# Connections.net
KiCad netlist of a schematic drawn in Altium Designer
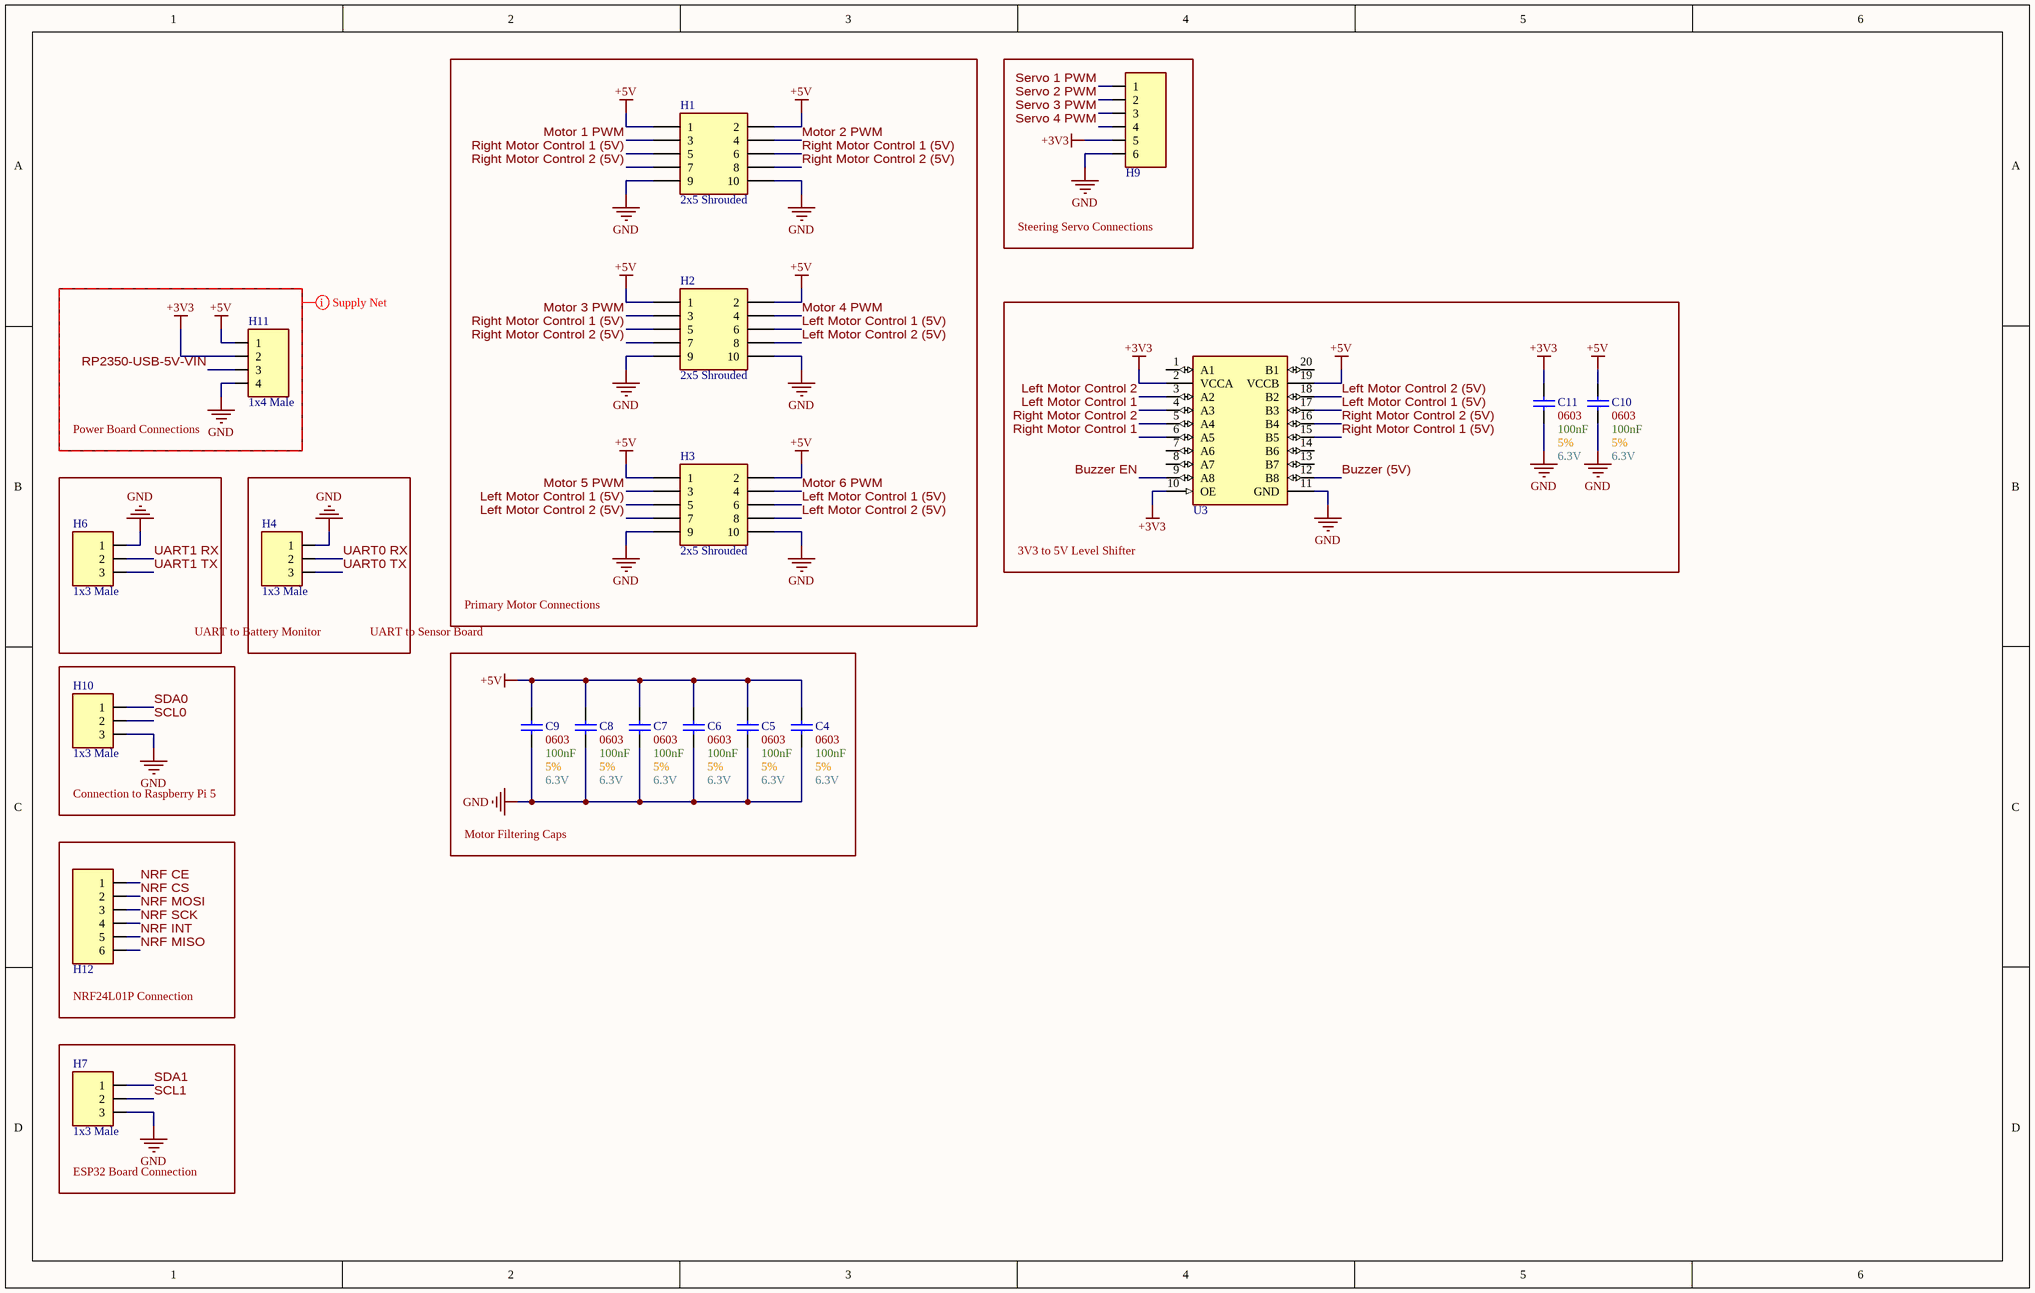
[diagram p0: Connections.SchDoc]

(export (version "E")
  (design (tool "Eeschema 10.0.6"))
  (components
    (comp (ref "C4")
      (value "[Cap] SMD Nonpolarized")
      (footprint "[Cap] SMD 0603")
      (fields
        (field (name "SIZE PACKAGE") "0603")
        (field (name "CAPACITANCE") "100nF")
        (field (name "VOLTAGE") "6.3V")
        (field (name "TOLERANCE") "5%")
      )
      (libsource (lib "RADM Components") (part "[Cap] SMD Nonpolarized"))
    )
    (comp (ref "C5")
      (value "[Cap] SMD Nonpolarized")
      (footprint "[Cap] SMD 0603")
      (fields
        (field (name "SIZE PACKAGE") "0603")
        (field (name "CAPACITANCE") "100nF")
        (field (name "VOLTAGE") "6.3V")
        (field (name "TOLERANCE") "5%")
      )
      (libsource (lib "RADM Components") (part "[Cap] SMD Nonpolarized"))
    )
    (comp (ref "C6")
      (value "[Cap] SMD Nonpolarized")
      (footprint "[Cap] SMD 0603")
      (fields
        (field (name "SIZE PACKAGE") "0603")
        (field (name "CAPACITANCE") "100nF")
        (field (name "VOLTAGE") "6.3V")
        (field (name "TOLERANCE") "5%")
      )
      (libsource (lib "RADM Components") (part "[Cap] SMD Nonpolarized"))
    )
    (comp (ref "C7")
      (value "[Cap] SMD Nonpolarized")
      (footprint "[Cap] SMD 0603")
      (fields
        (field (name "SIZE PACKAGE") "0603")
        (field (name "CAPACITANCE") "100nF")
        (field (name "VOLTAGE") "6.3V")
        (field (name "TOLERANCE") "5%")
      )
      (libsource (lib "RADM Components") (part "[Cap] SMD Nonpolarized"))
    )
    (comp (ref "C8")
      (value "[Cap] SMD Nonpolarized")
      (footprint "[Cap] SMD 0603")
      (fields
        (field (name "SIZE PACKAGE") "0603")
        (field (name "CAPACITANCE") "100nF")
        (field (name "VOLTAGE") "6.3V")
        (field (name "TOLERANCE") "5%")
      )
      (libsource (lib "RADM Components") (part "[Cap] SMD Nonpolarized"))
    )
    (comp (ref "C9")
      (value "[Cap] SMD Nonpolarized")
      (footprint "[Cap] SMD 0603")
      (fields
        (field (name "SIZE PACKAGE") "0603")
        (field (name "CAPACITANCE") "100nF")
        (field (name "VOLTAGE") "6.3V")
        (field (name "TOLERANCE") "5%")
      )
      (libsource (lib "RADM Components") (part "[Cap] SMD Nonpolarized"))
    )
    (comp (ref "C10")
      (value "[Cap] SMD Nonpolarized")
      (footprint "[Cap] SMD 0603")
      (fields
        (field (name "SIZE PACKAGE") "0603")
        (field (name "CAPACITANCE") "100nF")
        (field (name "VOLTAGE") "6.3V")
        (field (name "TOLERANCE") "5%")
      )
      (libsource (lib "RADM Components") (part "[Cap] SMD Nonpolarized"))
    )
    (comp (ref "C11")
      (value "[Cap] SMD Nonpolarized")
      (footprint "[Cap] SMD 0603")
      (fields
        (field (name "SIZE PACKAGE") "0603")
        (field (name "CAPACITANCE") "100nF")
        (field (name "VOLTAGE") "6.3V")
        (field (name "TOLERANCE") "5%")
      )
      (libsource (lib "RADM Components") (part "[Cap] SMD Nonpolarized"))
    )
    (comp (ref "H1")
      (value "2x5 Shrouded")
      (footprint "[Header] Shrouded 2x5 Male")
      (description "BHR-10-VUA")
      (libsource (lib "RADM Connectors") (part "[Header] Shrouded 2x5 Male"))
    )
    (comp (ref "H2")
      (value "2x5 Shrouded")
      (footprint "[Header] Shrouded 2x5 Male")
      (description "BHR-10-VUA")
      (libsource (lib "RADM Connectors") (part "[Header] Shrouded 2x5 Male"))
    )
    (comp (ref "H3")
      (value "2x5 Shrouded")
      (footprint "[Header] Shrouded 2x5 Male")
      (description "BHR-10-VUA")
      (libsource (lib "RADM Connectors") (part "[Header] Shrouded 2x5 Male"))
    )
    (comp (ref "H4")
      (value "1x3 Male")
      (footprint "[Header] Shrouded 1x3 Male")
      (description "070543-0037\r\nMates with 005057-9403")
      (libsource (lib "RADM Connectors") (part "[Header] Shrouded 1x3 Male"))
    )
    (comp (ref "H6")
      (value "1x3 Male")
      (footprint "[Header] Shrouded 1x3 Male")
      (description "070543-0037\r\nMates with 005057-9403")
      (libsource (lib "RADM Connectors") (part "[Header] Shrouded 1x3 Male"))
    )
    (comp (ref "H7")
      (value "1x3 Male")
      (footprint "[Header] Shrouded 1x3 Male")
      (description "070543-0037\r\nMates with 005057-9403")
      (libsource (lib "RADM Connectors") (part "[Header] Shrouded 1x3 Male"))
    )
    (comp (ref "H9")
      (value "[Header] Shrouded 1x6 Male")
      (footprint "[Header] Shrouded 1x6 Male")
      (description "0705430005\r\nMates with 0050579406")
      (libsource (lib "") (part "[Header] Shrouded 1x6 Male_1"))
    )
    (comp (ref "H10")
      (value "1x3 Male")
      (footprint "[Header] Shrouded 1x3 Male")
      (description "070543-0037\r\nMates with 005057-9403")
      (libsource (lib "RADM Connectors") (part "[Header] Shrouded 1x3 Male"))
    )
    (comp (ref "H11")
      (value "1x4 Male")
      (footprint "[Header] Shrouded 1x4 Male")
      (description "70543-0003\r\nMates with 005057-9404")
      (libsource (lib "RADM Connectors") (part "[Header] Shrouded 1x4 Male"))
    )
    (comp (ref "H12")
      (value "[Header] Shrouded 1x6 Male")
      (footprint "[Header] Shrouded 1x6 Male")
      (description "0705430005\r\nMates with 0050579406")
      (libsource (lib "RADM Connectors") (part "[Header] Shrouded 1x6 Male"))
    )
    (comp (ref "U3")
      (value "[IC] Level Shifter (2)")
      (footprint "[IC] Level Shifter (2)")
      (description "TXS0108EQPWRQ1")
      (libsource (lib "RADM Components") (part "[IC] Level Shifter (2)"))
    )
  )
  (nets
    (net (code "1") (name "+3V3") (class "Default")
      (node (ref "C11") (pin "2") (pinfunction "2_2") (pintype "passive"))
      (node (ref "H11") (pin "2") (pinfunction "2_2") (pintype "passive"))
      (node (ref "H9") (pin "5") (pinfunction "5_5") (pintype "passive"))
      (node (ref "U3") (pin "10") (pinfunction "OE_10") (pintype "input"))
      (node (ref "U3") (pin "2") (pinfunction "VCCA_2") (pintype "power_in"))
    )
    (net (code "2") (name "+5V") (class "Default")
      (node (ref "C10") (pin "2") (pinfunction "2_2") (pintype "passive"))
      (node (ref "C4") (pin "2") (pinfunction "2_2") (pintype "passive"))
      (node (ref "C5") (pin "2") (pinfunction "2_2") (pintype "passive"))
      (node (ref "C6") (pin "2") (pinfunction "2_2") (pintype "passive"))
      (node (ref "C7") (pin "2") (pinfunction "2_2") (pintype "passive"))
      (node (ref "C8") (pin "2") (pinfunction "2_2") (pintype "passive"))
      (node (ref "C9") (pin "2") (pinfunction "2_2") (pintype "passive"))
      (node (ref "H1") (pin "1") (pinfunction "1_1") (pintype "passive"))
      (node (ref "H1") (pin "2") (pinfunction "2_2") (pintype "passive"))
      (node (ref "H11") (pin "1") (pinfunction "1_1") (pintype "passive"))
      (node (ref "H2") (pin "1") (pinfunction "1_1") (pintype "passive"))
      (node (ref "H2") (pin "2") (pinfunction "2_2") (pintype "passive"))
      (node (ref "H3") (pin "1") (pinfunction "1_1") (pintype "passive"))
      (node (ref "H3") (pin "2") (pinfunction "2_2") (pintype "passive"))
      (node (ref "U3") (pin "19") (pinfunction "VCCB_19") (pintype "power_in"))
    )
    (net (code "3") (name "/Buzzer (5V)") (class "Default")
      (node (ref "U3") (pin "12") (pinfunction "B8_12") (pintype "bidirectional"))
    )
    (net (code "4") (name "/Buzzer EN") (class "Default")
      (node (ref "U3") (pin "9") (pinfunction "A8_9") (pintype "bidirectional"))
    )
    (net (code "5") (name "/Left Motor Control 1") (class "Default")
      (node (ref "U3") (pin "4") (pinfunction "A3_4") (pintype "bidirectional"))
    )
    (net (code "6") (name "/Left Motor Control 1 (5V)") (class "Default")
      (node (ref "H2") (pin "6") (pinfunction "6_6") (pintype "passive"))
      (node (ref "H3") (pin "5") (pinfunction "5_5") (pintype "passive"))
      (node (ref "H3") (pin "6") (pinfunction "6_6") (pintype "passive"))
      (node (ref "U3") (pin "17") (pinfunction "B3_17") (pintype "bidirectional"))
    )
    (net (code "7") (name "/Left Motor Control 2") (class "Default")
      (node (ref "U3") (pin "3") (pinfunction "A2_3") (pintype "bidirectional"))
    )
    (net (code "8") (name "/Left Motor Control 2 (5V)") (class "Default")
      (node (ref "H2") (pin "8") (pinfunction "8_8") (pintype "passive"))
      (node (ref "H3") (pin "7") (pinfunction "7_7") (pintype "passive"))
      (node (ref "H3") (pin "8") (pinfunction "8_8") (pintype "passive"))
      (node (ref "U3") (pin "18") (pinfunction "B2_18") (pintype "bidirectional"))
    )
    (net (code "9") (name "/Motor 1 PWM") (class "Default")
      (node (ref "H1") (pin "3") (pinfunction "3_3") (pintype "passive"))
    )
    (net (code "10") (name "/Motor 2 PWM") (class "Default")
      (node (ref "H1") (pin "4") (pinfunction "4_4") (pintype "passive"))
    )
    (net (code "11") (name "/Motor 3 PWM") (class "Default")
      (node (ref "H2") (pin "3") (pinfunction "3_3") (pintype "passive"))
    )
    (net (code "12") (name "/Motor 4 PWM") (class "Default")
      (node (ref "H2") (pin "4") (pinfunction "4_4") (pintype "passive"))
    )
    (net (code "13") (name "/Motor 5 PWM") (class "Default")
      (node (ref "H3") (pin "3") (pinfunction "3_3") (pintype "passive"))
    )
    (net (code "14") (name "/Motor 6 PWM") (class "Default")
      (node (ref "H3") (pin "4") (pinfunction "4_4") (pintype "passive"))
    )
    (net (code "15") (name "/NRF CE") (class "Default")
      (node (ref "H12") (pin "1") (pinfunction "1_1") (pintype "passive"))
    )
    (net (code "16") (name "/NRF CS") (class "Default")
      (node (ref "H12") (pin "2") (pinfunction "2_2") (pintype "passive"))
    )
    (net (code "17") (name "/NRF INT") (class "Default")
      (node (ref "H12") (pin "5") (pinfunction "5_5") (pintype "passive"))
    )
    (net (code "18") (name "/NRF MISO") (class "Default")
      (node (ref "H12") (pin "6") (pinfunction "6_6") (pintype "passive"))
    )
    (net (code "19") (name "/NRF MOSI") (class "Default")
      (node (ref "H12") (pin "3") (pinfunction "3_3") (pintype "passive"))
    )
    (net (code "20") (name "/NRF SCK") (class "Default")
      (node (ref "H12") (pin "4") (pinfunction "4_4") (pintype "passive"))
    )
    (net (code "21") (name "/RP2350-USB-5V-VIN") (class "Default")
      (node (ref "H11") (pin "3") (pinfunction "3_3") (pintype "passive"))
    )
    (net (code "22") (name "/Right Motor Control 1") (class "Default")
      (node (ref "U3") (pin "6") (pinfunction "A5_6") (pintype "bidirectional"))
    )
    (net (code "23") (name "/Right Motor Control 1 (5V)") (class "Default")
      (node (ref "H1") (pin "5") (pinfunction "5_5") (pintype "passive"))
      (node (ref "H1") (pin "6") (pinfunction "6_6") (pintype "passive"))
      (node (ref "H2") (pin "5") (pinfunction "5_5") (pintype "passive"))
      (node (ref "U3") (pin "15") (pinfunction "B5_15") (pintype "bidirectional"))
    )
    (net (code "24") (name "/Right Motor Control 2") (class "Default")
      (node (ref "U3") (pin "5") (pinfunction "A4_5") (pintype "bidirectional"))
    )
    (net (code "25") (name "/Right Motor Control 2 (5V)") (class "Default")
      (node (ref "H1") (pin "7") (pinfunction "7_7") (pintype "passive"))
      (node (ref "H1") (pin "8") (pinfunction "8_8") (pintype "passive"))
      (node (ref "H2") (pin "7") (pinfunction "7_7") (pintype "passive"))
      (node (ref "U3") (pin "16") (pinfunction "B4_16") (pintype "bidirectional"))
    )
    (net (code "26") (name "/SCL0") (class "Default")
      (node (ref "H10") (pin "2") (pinfunction "2_2") (pintype "passive"))
    )
    (net (code "27") (name "/SCL1") (class "Default")
      (node (ref "H7") (pin "2") (pinfunction "2_2") (pintype "passive"))
    )
    (net (code "28") (name "/SDA0") (class "Default")
      (node (ref "H10") (pin "1") (pinfunction "1_1") (pintype "passive"))
    )
    (net (code "29") (name "/SDA1") (class "Default")
      (node (ref "H7") (pin "1") (pinfunction "1_1") (pintype "passive"))
    )
    (net (code "30") (name "/Servo 1 PWM") (class "Default")
      (node (ref "H9") (pin "1") (pinfunction "1_1") (pintype "passive"))
    )
    (net (code "31") (name "/Servo 2 PWM") (class "Default")
      (node (ref "H9") (pin "2") (pinfunction "2_2") (pintype "passive"))
    )
    (net (code "32") (name "/Servo 3 PWM") (class "Default")
      (node (ref "H9") (pin "3") (pinfunction "3_3") (pintype "passive"))
    )
    (net (code "33") (name "/Servo 4 PWM") (class "Default")
      (node (ref "H9") (pin "4") (pinfunction "4_4") (pintype "passive"))
    )
    (net (code "34") (name "/UART0 RX") (class "Default")
      (node (ref "H4") (pin "2") (pinfunction "2_2") (pintype "passive"))
    )
    (net (code "35") (name "/UART0 TX") (class "Default")
      (node (ref "H4") (pin "3") (pinfunction "3_3") (pintype "passive"))
    )
    (net (code "36") (name "/UART1 RX") (class "Default")
      (node (ref "H6") (pin "2") (pinfunction "2_2") (pintype "passive"))
    )
    (net (code "37") (name "/UART1 TX") (class "Default")
      (node (ref "H6") (pin "3") (pinfunction "3_3") (pintype "passive"))
    )
    (net (code "38") (name "GND") (class "Default")
      (node (ref "C10") (pin "1") (pinfunction "1_1") (pintype "passive"))
      (node (ref "C11") (pin "1") (pinfunction "1_1") (pintype "passive"))
      (node (ref "C4") (pin "1") (pinfunction "1_1") (pintype "passive"))
      (node (ref "C5") (pin "1") (pinfunction "1_1") (pintype "passive"))
      (node (ref "C6") (pin "1") (pinfunction "1_1") (pintype "passive"))
      (node (ref "C7") (pin "1") (pinfunction "1_1") (pintype "passive"))
      (node (ref "C8") (pin "1") (pinfunction "1_1") (pintype "passive"))
      (node (ref "C9") (pin "1") (pinfunction "1_1") (pintype "passive"))
      (node (ref "H1") (pin "10") (pinfunction "10_10") (pintype "passive"))
      (node (ref "H1") (pin "9") (pinfunction "9_9") (pintype "passive"))
      (node (ref "H10") (pin "3") (pinfunction "3_3") (pintype "passive"))
      (node (ref "H11") (pin "4") (pinfunction "4_4") (pintype "passive"))
      (node (ref "H2") (pin "10") (pinfunction "10_10") (pintype "passive"))
      (node (ref "H2") (pin "9") (pinfunction "9_9") (pintype "passive"))
      (node (ref "H3") (pin "10") (pinfunction "10_10") (pintype "passive"))
      (node (ref "H3") (pin "9") (pinfunction "9_9") (pintype "passive"))
      (node (ref "H4") (pin "1") (pinfunction "1_1") (pintype "passive"))
      (node (ref "H6") (pin "1") (pinfunction "1_1") (pintype "passive"))
      (node (ref "H7") (pin "3") (pinfunction "3_3") (pintype "passive"))
      (node (ref "H9") (pin "6") (pinfunction "6_6") (pintype "passive"))
      (node (ref "U3") (pin "11") (pinfunction "GND_11") (pintype "power_in"))
    )
    (net (code "39") (name "unconnected-(U3-A1-Pad1)") (class "Default")
      (node (ref "U3") (pin "1") (pinfunction "A1_1") (pintype "bidirectional"))
    )
    (net (code "40") (name "unconnected-(U3-A6-Pad7)") (class "Default")
      (node (ref "U3") (pin "7") (pinfunction "A6_7") (pintype "bidirectional"))
    )
    (net (code "41") (name "unconnected-(U3-A7-Pad8)") (class "Default")
      (node (ref "U3") (pin "8") (pinfunction "A7_8") (pintype "bidirectional"))
    )
    (net (code "42") (name "unconnected-(U3-B1-Pad20)") (class "Default")
      (node (ref "U3") (pin "20") (pinfunction "B1_20") (pintype "bidirectional"))
    )
    (net (code "43") (name "unconnected-(U3-B6-Pad14)") (class "Default")
      (node (ref "U3") (pin "14") (pinfunction "B6_14") (pintype "bidirectional"))
    )
    (net (code "44") (name "unconnected-(U3-B7-Pad13)") (class "Default")
      (node (ref "U3") (pin "13") (pinfunction "B7_13") (pintype "bidirectional"))
    )
  )
)
